# Sheet1.net
KiCad netlist of a schematic drawn in Altium Designer
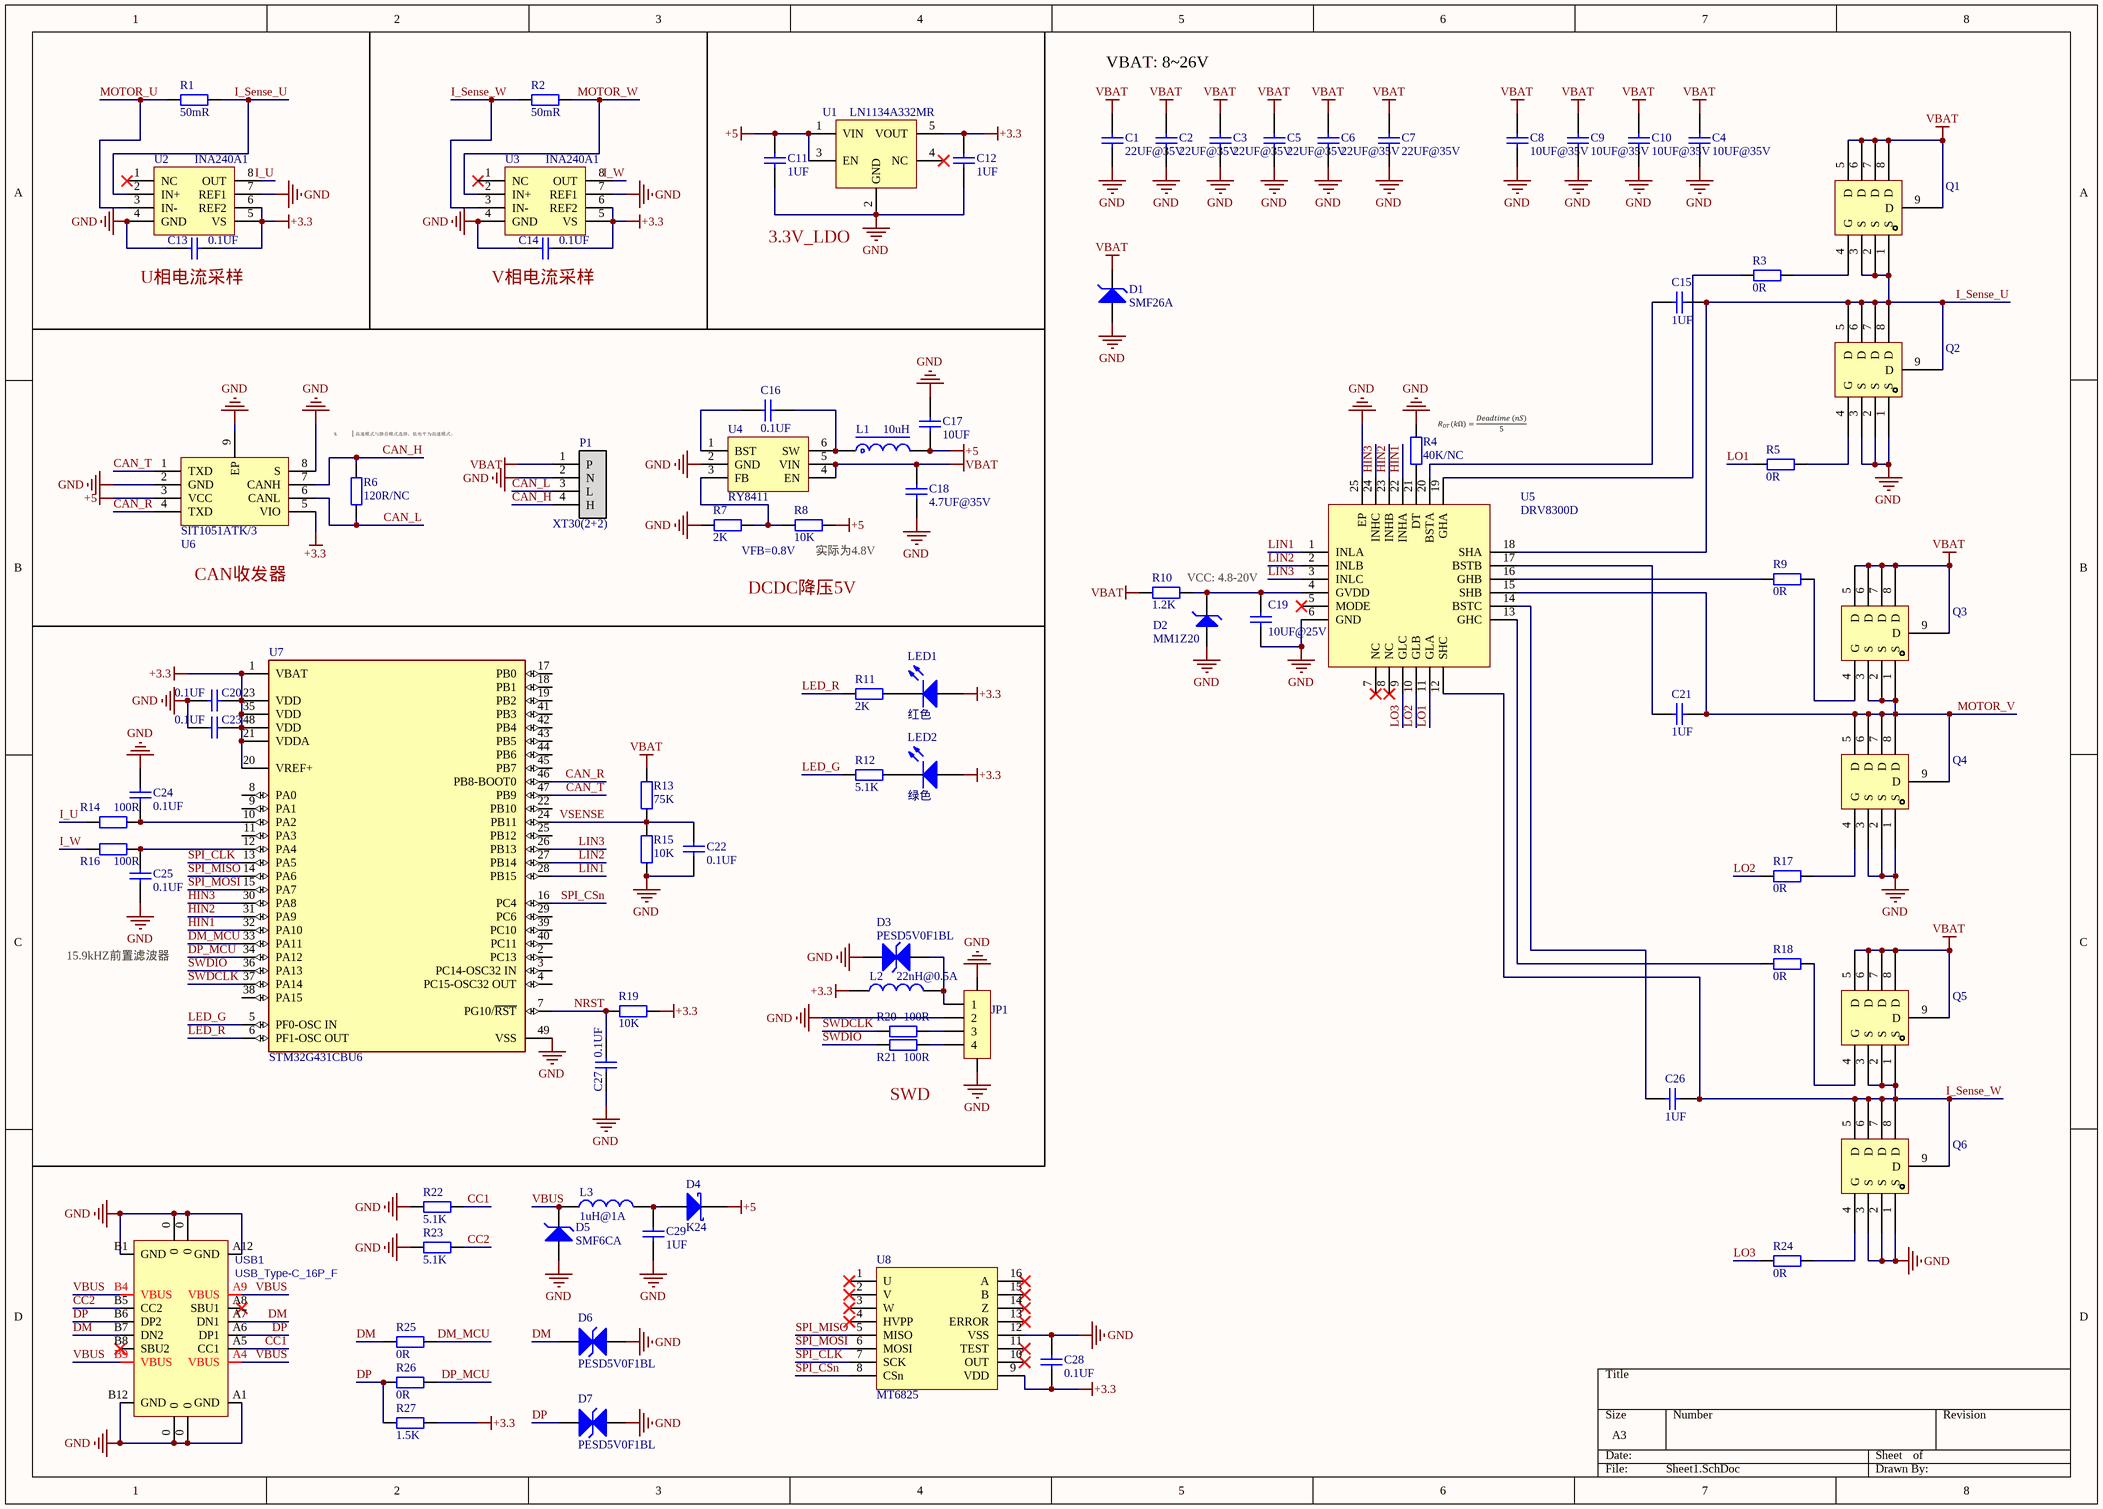
[diagram p0: Sheet1.SchDoc]

(export (version "E")
  (design (tool "Eeschema 10.0.6"))
  (components
    (comp (ref "C1")
      (value "22UF@35V")
      (footprint "C1206_NS")
      (description "贴片电容/MLCC电容")
      (libsource (lib "阻容") (part "C"))
    )
    (comp (ref "C2")
      (value "22UF@35V")
      (footprint "C1206_NS")
      (description "贴片电容/MLCC电容")
      (libsource (lib "阻容") (part "C"))
    )
    (comp (ref "C3")
      (value "22UF@35V")
      (footprint "C1206_NS")
      (description "贴片电容/MLCC电容")
      (libsource (lib "阻容") (part "C"))
    )
    (comp (ref "C4")
      (value "10UF@35V")
      (footprint "C0805_NS")
      (description "贴片电容/MLCC电容")
      (libsource (lib "阻容") (part "C"))
    )
    (comp (ref "C5")
      (value "22UF@35V")
      (footprint "C1206_NS")
      (description "贴片电容/MLCC电容")
      (libsource (lib "阻容") (part "C"))
    )
    (comp (ref "C6")
      (value "22UF@35V")
      (footprint "C1206_NS")
      (description "贴片电容/MLCC电容")
      (libsource (lib "阻容") (part "C"))
    )
    (comp (ref "C7")
      (value "22UF@35V")
      (footprint "C1206_NS")
      (description "贴片电容/MLCC电容")
      (libsource (lib "阻容") (part "C"))
    )
    (comp (ref "C8")
      (value "10UF@35V")
      (footprint "C0805_NS")
      (description "贴片电容/MLCC电容")
      (libsource (lib "阻容") (part "C"))
    )
    (comp (ref "C9")
      (value "10UF@35V")
      (footprint "C0805_NS")
      (description "贴片电容/MLCC电容")
      (libsource (lib "阻容") (part "C"))
    )
    (comp (ref "C10")
      (value "10UF@35V")
      (footprint "C0805_NS")
      (description "贴片电容/MLCC电容")
      (libsource (lib "阻容") (part "C"))
    )
    (comp (ref "C11")
      (value "1UF")
      (footprint "C0402_NS")
      (description "贴片电容/MLCC电容")
      (libsource (lib "阻容") (part "C"))
    )
    (comp (ref "C12")
      (value "1UF")
      (footprint "C0402_NS")
      (description "贴片电容/MLCC电容")
      (libsource (lib "阻容") (part "C"))
    )
    (comp (ref "C13")
      (value "0.1UF")
      (footprint "C0402_NS")
      (description "贴片电容/MLCC电容")
      (libsource (lib "阻容") (part "C"))
    )
    (comp (ref "C14")
      (value "0.1UF")
      (footprint "C0402_NS")
      (description "贴片电容/MLCC电容")
      (libsource (lib "阻容") (part "C"))
    )
    (comp (ref "C15")
      (value "1UF")
      (footprint "C0603_NS")
      (description "贴片电容/MLCC电容")
      (libsource (lib "阻容") (part "C"))
    )
    (comp (ref "C16")
      (value "0.1UF")
      (footprint "C0402_NS")
      (description "贴片电容/MLCC电容")
      (libsource (lib "阻容") (part "C"))
    )
    (comp (ref "C17")
      (value "10UF")
      (footprint "C0805_NS")
      (description "贴片电容/MLCC电容")
      (libsource (lib "阻容") (part "C"))
    )
    (comp (ref "C18")
      (value "4.7UF@35V")
      (footprint "C0805_NS")
      (description "贴片电容/MLCC电容")
      (libsource (lib "阻容") (part "C"))
    )
    (comp (ref "C19")
      (value "10UF@25V")
      (footprint "C0603_NS")
      (description "贴片电容/MLCC电容")
      (libsource (lib "阻容") (part "C"))
    )
    (comp (ref "C20")
      (value "0.1UF")
      (footprint "C0402_NS")
      (description "贴片电容/MLCC电容")
      (libsource (lib "阻容") (part "C"))
    )
    (comp (ref "C21")
      (value "1UF")
      (footprint "C0603_NS")
      (description "贴片电容/MLCC电容")
      (libsource (lib "阻容") (part "C"))
    )
    (comp (ref "C22")
      (value "0.1UF")
      (footprint "C0402_NS")
      (description "贴片电容/MLCC电容")
      (libsource (lib "阻容") (part "C"))
    )
    (comp (ref "C23")
      (value "0.1UF")
      (footprint "C0402_NS")
      (description "贴片电容/MLCC电容")
      (libsource (lib "阻容") (part "C"))
    )
    (comp (ref "C24")
      (value "0.1UF")
      (footprint "C0402_NS")
      (description "贴片电容/MLCC电容")
      (libsource (lib "阻容") (part "C"))
    )
    (comp (ref "C25")
      (value "0.1UF")
      (footprint "C0402_NS")
      (description "贴片电容/MLCC电容")
      (libsource (lib "阻容") (part "C"))
    )
    (comp (ref "C26")
      (value "1UF")
      (footprint "C0603_NS")
      (description "贴片电容/MLCC电容")
      (libsource (lib "阻容") (part "C"))
    )
    (comp (ref "C27")
      (value "0.1UF")
      (footprint "C0402_NS")
      (description "贴片电容/MLCC电容")
      (libsource (lib "阻容") (part "C"))
    )
    (comp (ref "C28")
      (value "0.1UF")
      (footprint "C0402_NS")
      (description "贴片电容/MLCC电容")
      (libsource (lib "阻容") (part "C"))
    )
    (comp (ref "C29")
      (value "1UF")
      (footprint "C0603_NS")
      (description "贴片电容/MLCC电容")
      (libsource (lib "阻容") (part "C"))
    )
    (comp (ref "D1")
      (value "SMF26A")
      (footprint "SOD-123")
      (description "TVS通用")
      (libsource (lib "二极管(含LED)") (part "TVS"))
    )
    (comp (ref "D2")
      (value "MM1Z20")
      (footprint "SOD-123")
      (description "稳压二极管")
      (fields (field (name "VOLTAGE") "5.1V"))
      (libsource (lib "二极管(含LED)") (part "MM1ZXX"))
    )
    (comp (ref "D3")
      (value "PESD5V0F1BL")
      (footprint "DFN1002-2L_L1.0_W0.6_P0.7")
      (description "双向静电和浪涌保护(TVS/ESD)")
      (libsource (lib "二极管(含LED)") (part "PESD5V0F1BL"))
    )
    (comp (ref "D4")
      (value "K24")
      (footprint "SOD-123")
      (description "肖特基二极管")
      (libsource (lib "二极管(含LED)") (part "SSXX"))
    )
    (comp (ref "D5")
      (value "SMF6CA")
      (footprint "SOD-123")
      (description "TVS通用")
      (libsource (lib "二极管(含LED)") (part "TVS"))
    )
    (comp (ref "D6")
      (value "PESD5V0F1BL")
      (footprint "DFN1002-2L_L1.0_W0.6_P0.7")
      (description "双向静电和浪涌保护(TVS/ESD)")
      (libsource (lib "二极管(含LED)") (part "PESD5V0F1BL"))
    )
    (comp (ref "D7")
      (value "PESD5V0F1BL")
      (footprint "DFN1002-2L_L1.0_W0.6_P0.7")
      (description "双向静电和浪涌保护(TVS/ESD)")
      (libsource (lib "二极管(含LED)") (part "PESD5V0F1BL"))
    )
    (comp (ref "JP1")
      (value "CON-4P")
      (footprint "HC0.8-WT-4P")
      (description "4P连接器")
      (libsource (lib "0.80mm连接器") (part "Header 4"))
    )
    (comp (ref "L1")
      (value "10uH")
      (footprint "NR3015")
      (description "太诱-NR磁胶电感")
      (libsource (lib "电感") (part "L-NR"))
    )
    (comp (ref "L2")
      (value "22nH@0.5A")
      (footprint "L0402_NS")
      (description "小功率贴片电感")
      (libsource (lib "电感") (part "L"))
    )
    (comp (ref "L3")
      (value "1uH@1A")
      (footprint "L1206_NS")
      (description "小功率贴片电感")
      (libsource (lib "电感") (part "L"))
    )
    (comp (ref "LED1")
      (value "红色")
      (footprint "LED0402_NS")
      (description "贴片LED")
      (libsource (lib "二极管(含LED)") (part "LED"))
    )
    (comp (ref "LED2")
      (value "绿色")
      (footprint "LED0402_NS")
      (description "贴片LED")
      (libsource (lib "二极管(含LED)") (part "LED"))
    )
    (comp (ref "P1")
      (value "XT30(2+2)")
      (footprint "XT30(2+2)PW-M")
      (description "XT30(2+2)连接器")
      (libsource (lib "接口") (part "XT30(2+2)"))
    )
    (comp (ref "Q1")
      (value "WSD3066DN33")
      (footprint "DFN8_L3.3_W3.3_P0.65")
      (libsource (lib "三极管-MOS管") (part "WSD3066DN33"))
    )
    (comp (ref "Q2")
      (value "WSD3066DN33")
      (footprint "DFN8_L3.3_W3.3_P0.65")
      (libsource (lib "三极管-MOS管") (part "WSD3066DN33"))
    )
    (comp (ref "Q3")
      (value "WSD3066DN33")
      (footprint "DFN8_L3.3_W3.3_P0.65")
      (libsource (lib "三极管-MOS管") (part "WSD3066DN33"))
    )
    (comp (ref "Q4")
      (value "WSD3066DN33")
      (footprint "DFN8_L3.3_W3.3_P0.65")
      (libsource (lib "三极管-MOS管") (part "WSD3066DN33"))
    )
    (comp (ref "Q5")
      (value "WSD3066DN33")
      (footprint "DFN8_L3.3_W3.3_P0.65")
      (libsource (lib "三极管-MOS管") (part "WSD3066DN33"))
    )
    (comp (ref "Q6")
      (value "WSD3066DN33")
      (footprint "DFN8_L3.3_W3.3_P0.65")
      (libsource (lib "三极管-MOS管") (part "WSD3066DN33"))
    )
    (comp (ref "R1")
      (value "50mR")
      (footprint "R1206_NS")
      (description "贴片电阻")
      (libsource (lib "阻容") (part "R"))
    )
    (comp (ref "R2")
      (value "50mR")
      (footprint "R1206_NS")
      (description "贴片电阻")
      (libsource (lib "阻容") (part "R"))
    )
    (comp (ref "R3")
      (value "0R")
      (footprint "R0402_NS")
      (description "贴片电阻")
      (libsource (lib "阻容") (part "R"))
    )
    (comp (ref "R4")
      (value "40K/NC")
      (footprint "R0402_NS")
      (description "贴片电阻")
      (libsource (lib "阻容") (part "R"))
    )
    (comp (ref "R5")
      (value "0R")
      (footprint "R0402_NS")
      (description "贴片电阻")
      (libsource (lib "阻容") (part "R"))
    )
    (comp (ref "R6")
      (value "120R/NC")
      (footprint "R0603_NS")
      (description "贴片电阻")
      (libsource (lib "阻容") (part "R"))
    )
    (comp (ref "R7")
      (value "2K")
      (footprint "R0402_NS")
      (description "贴片电阻")
      (libsource (lib "阻容") (part "R"))
    )
    (comp (ref "R8")
      (value "10K")
      (footprint "R0402_NS")
      (description "贴片电阻")
      (libsource (lib "阻容") (part "R"))
    )
    (comp (ref "R9")
      (value "0R")
      (footprint "R0402_NS")
      (description "贴片电阻")
      (libsource (lib "阻容") (part "R"))
    )
    (comp (ref "R10")
      (value "1.2K")
      (footprint "R0603_NS")
      (description "贴片电阻")
      (libsource (lib "阻容") (part "R"))
    )
    (comp (ref "R11")
      (value "2K")
      (footprint "R0402_NS")
      (description "贴片电阻")
      (libsource (lib "阻容") (part "R"))
    )
    (comp (ref "R12")
      (value "5.1K")
      (footprint "R0402_NS")
      (description "贴片电阻")
      (libsource (lib "阻容") (part "R"))
    )
    (comp (ref "R13")
      (value "75K")
      (footprint "R0402_NS")
      (description "贴片电阻")
      (libsource (lib "阻容") (part "R"))
    )
    (comp (ref "R14")
      (value "100R")
      (footprint "R0402_NS")
      (description "贴片电阻")
      (libsource (lib "阻容") (part "R"))
    )
    (comp (ref "R15")
      (value "10K")
      (footprint "R0402_NS")
      (description "贴片电阻")
      (libsource (lib "阻容") (part "R"))
    )
    (comp (ref "R16")
      (value "100R")
      (footprint "R0402_NS")
      (description "贴片电阻")
      (libsource (lib "阻容") (part "R"))
    )
    (comp (ref "R17")
      (value "0R")
      (footprint "R0402_NS")
      (description "贴片电阻")
      (libsource (lib "阻容") (part "R"))
    )
    (comp (ref "R18")
      (value "0R")
      (footprint "R0402_NS")
      (description "贴片电阻")
      (libsource (lib "阻容") (part "R"))
    )
    (comp (ref "R19")
      (value "10K")
      (footprint "R0402_NS")
      (description "贴片电阻")
      (libsource (lib "阻容") (part "R"))
    )
    (comp (ref "R20")
      (value "100R")
      (footprint "R0402_NS")
      (description "贴片电阻")
      (libsource (lib "阻容") (part "R"))
    )
    (comp (ref "R21")
      (value "100R")
      (footprint "R0402_NS")
      (description "贴片电阻")
      (libsource (lib "阻容") (part "R"))
    )
    (comp (ref "R22")
      (value "5.1K")
      (footprint "R0402_NS")
      (description "贴片电阻")
      (libsource (lib "阻容") (part "R"))
    )
    (comp (ref "R23")
      (value "5.1K")
      (footprint "R0402_NS")
      (description "贴片电阻")
      (libsource (lib "阻容") (part "R"))
    )
    (comp (ref "R24")
      (value "0R")
      (footprint "R0402_NS")
      (description "贴片电阻")
      (libsource (lib "阻容") (part "R"))
    )
    (comp (ref "R25")
      (value "0R")
      (footprint "R0402_NS")
      (description "贴片电阻")
      (libsource (lib "阻容") (part "R"))
    )
    (comp (ref "R26")
      (value "0R")
      (footprint "R0402_NS")
      (description "贴片电阻")
      (libsource (lib "阻容") (part "R"))
    )
    (comp (ref "R27")
      (value "1.5K")
      (footprint "R0402_NS")
      (description "贴片电阻")
      (libsource (lib "阻容") (part "R"))
    )
    (comp (ref "U1")
      (value "LN1134A332MR")
      (footprint "SOT23-5_L3.0_W1.7_P0.95")
      (libsource (lib "LDO") (part "RT9013-33GB"))
    )
    (comp (ref "U2")
      (value "INA240A1")
      (footprint "TSSOP8_L4.4_W3.0_P0.65")
      (description "具有增强的 PWM 抑制能力的 -4V 至 80V、双向、超精密电流感应放大器")
      (libsource (lib "运放") (part "INA240"))
    )
    (comp (ref "U3")
      (value "INA240A1")
      (footprint "TSSOP8_L4.4_W3.0_P0.65")
      (description "具有增强的 PWM 抑制能力的 -4V 至 80V、双向、超精密电流感应放大器")
      (libsource (lib "运放") (part "INA240"))
    )
    (comp (ref "U4")
      (value "RY8411")
      (footprint "SOT23-6_L3.0_W1.7_P0.95")
      (description "40V/1A/1.1MHz同步降压转换器")
      (libsource (lib "电源IC") (part "JW5026"))
    )
    (comp (ref "U5")
      (value "DRV8300D")
      (footprint "QFN24_L4.0_W4.0_P0.5")
      (description "具有自举二极管的最大 100V 简单三相栅极驱动器")
      (libsource (lib "电机驱动IC") (part "DRV8300D"))
    )
    (comp (ref "U6")
      (value "SIT1051ATK/3")
      (footprint "DFN8_L3.0_W3.0_P0.65")
      (description "5V 供电， IO 口兼容 3.3V，± 70V 总线耐压， CAN FD 静音模式总线收发器")
      (libsource (lib "协议芯片") (part "SIT1051ATK/3"))
    )
    (comp (ref "U7")
      (value "STM32G431CBU6")
      (footprint "QFN48_L7.0_W7.0_P0.5")
      (description "Microcontroller 32-Bit ARM Cortex-M4 RISC 128KB Flash 1.71V to 3.6V QFN48")
      (fields
        (field (name "MANUFACTURER") "STMicroelectronics")
        (field (name "OCTOPART") "https://octopart.com/stm32g431cbt6-stmicroelectronics-98835224")
      )
      (libsource (lib "2.1 - STM32 G0及G4系列单片机") (part "STM32G431CBU6"))
    )
    (comp (ref "U8")
      (value "MT6825")
      (footprint "TSSOP16_L5.0_W4.4_P0.65")
      (description "18位高分辨率、高速磁性角度编码器IC")
      (libsource (lib "其他") (part "MT6825"))
    )
    (comp (ref "USB1")
      (value "USB_Type-C_16P_F")
      (footprint "USB_Type-C_SMD_16P_F")
      (description "USB_Type-C母座")
      (libsource (lib "接口") (part "USB_Type-C_16P_F"))
    )
  )
  (nets
    (net (code "1") (name "+3.3") (class "Default")
      (node (ref "C12") (pin "2") (pinfunction "2_2") (pintype "passive"))
      (node (ref "C13") (pin "2") (pinfunction "2_2") (pintype "passive"))
      (node (ref "C14") (pin "2") (pinfunction "2_2") (pintype "passive"))
      (node (ref "C20") (pin "1") (pinfunction "1_1") (pintype "passive"))
      (node (ref "C23") (pin "1") (pinfunction "1_1") (pintype "passive"))
      (node (ref "C28") (pin "2") (pinfunction "2_2") (pintype "passive"))
      (node (ref "L2") (pin "1") (pinfunction "1_1") (pintype "passive"))
      (node (ref "LED1") (pin "1") (pinfunction "A_1") (pintype "passive"))
      (node (ref "LED2") (pin "1") (pinfunction "A_1") (pintype "passive"))
      (node (ref "R19") (pin "2") (pinfunction "2_2") (pintype "passive"))
      (node (ref "R27") (pin "2") (pinfunction "2_2") (pintype "passive"))
      (node (ref "U1") (pin "5") (pinfunction "VOUT_5") (pintype "passive"))
      (node (ref "U2") (pin "5") (pinfunction "VS_5") (pintype "passive"))
      (node (ref "U2") (pin "6") (pinfunction "REF2_6") (pintype "passive"))
      (node (ref "U3") (pin "5") (pinfunction "VS_5") (pintype "passive"))
      (node (ref "U3") (pin "6") (pinfunction "REF2_6") (pintype "passive"))
      (node (ref "U6") (pin "5") (pinfunction "VIO_5") (pintype "passive"))
      (node (ref "U7") (pin "1") (pinfunction "VBAT_1") (pintype "power_in"))
      (node (ref "U7") (pin "20") (pinfunction "VREF+_20") (pintype "power_in"))
      (node (ref "U7") (pin "21") (pinfunction "VDDA_21") (pintype "power_in"))
      (node (ref "U7") (pin "23") (pinfunction "VDD_23") (pintype "power_in"))
      (node (ref "U7") (pin "35") (pinfunction "VDD_35") (pintype "power_in"))
      (node (ref "U7") (pin "48") (pinfunction "VDD_48") (pintype "power_in"))
      (node (ref "U8") (pin "9") (pinfunction "VDD_9") (pintype "passive"))
    )
    (net (code "2") (name "+5") (class "Default")
      (node (ref "C11") (pin "2") (pinfunction "2_2") (pintype "passive"))
      (node (ref "C17") (pin "2") (pinfunction "2_2") (pintype "passive"))
      (node (ref "D4") (pin "2") (pinfunction "K_2") (pintype "passive"))
      (node (ref "L1") (pin "2") (pinfunction "2_2") (pintype "passive"))
      (node (ref "R8") (pin "1") (pinfunction "1_1") (pintype "passive"))
      (node (ref "U1") (pin "1") (pinfunction "VIN_1") (pintype "passive"))
      (node (ref "U1") (pin "3") (pinfunction "EN_3") (pintype "passive"))
      (node (ref "U6") (pin "3") (pinfunction "VCC_3") (pintype "passive"))
    )
    (net (code "3") (name "/CAN_H") (class "Default")
      (node (ref "P1") (pin "4") (pinfunction "H_4") (pintype "passive"))
      (node (ref "R6") (pin "2") (pinfunction "2_2") (pintype "passive"))
      (node (ref "U6") (pin "7") (pinfunction "CANH_7") (pintype "passive"))
    )
    (net (code "4") (name "/CAN_L") (class "Default")
      (node (ref "P1") (pin "3") (pinfunction "L_3") (pintype "passive"))
      (node (ref "R6") (pin "1") (pinfunction "1_1") (pintype "passive"))
      (node (ref "U6") (pin "6") (pinfunction "CANL_6") (pintype "passive"))
    )
    (net (code "5") (name "/CAN_R") (class "Default")
      (node (ref "U6") (pin "4") (pinfunction "TXD_4") (pintype "passive"))
      (node (ref "U7") (pin "46") (pinfunction "PB8-BOOT0_46") (pintype "bidirectional"))
    )
    (net (code "6") (name "/CAN_T") (class "Default")
      (node (ref "U6") (pin "1") (pinfunction "TXD_1") (pintype "passive"))
      (node (ref "U7") (pin "47") (pinfunction "PB9_47") (pintype "bidirectional"))
    )
    (net (code "7") (name "/CC1") (class "Default")
      (node (ref "R22") (pin "2") (pinfunction "2_2") (pintype "passive"))
      (node (ref "USB1") (pin "A5") (pinfunction "CC1_A5") (pintype "passive"))
    )
    (net (code "8") (name "/CC2") (class "Default")
      (node (ref "R23") (pin "2") (pinfunction "2_2") (pintype "passive"))
      (node (ref "USB1") (pin "B5") (pinfunction "CC2_B5") (pintype "passive"))
    )
    (net (code "9") (name "/DM") (class "Default")
      (node (ref "D6") (pin "1") (pinfunction "A_1") (pintype "passive"))
      (node (ref "R25") (pin "1") (pinfunction "1_1") (pintype "passive"))
      (node (ref "USB1") (pin "A7") (pinfunction "DN1_A7") (pintype "passive"))
      (node (ref "USB1") (pin "B7") (pinfunction "DN2_B7") (pintype "passive"))
    )
    (net (code "10") (name "/DM_MCU") (class "Default")
      (node (ref "R25") (pin "2") (pinfunction "2_2") (pintype "passive"))
      (node (ref "U7") (pin "33") (pinfunction "PA11_33") (pintype "bidirectional"))
    )
    (net (code "11") (name "/DP") (class "Default")
      (node (ref "D7") (pin "1") (pinfunction "A_1") (pintype "passive"))
      (node (ref "R26") (pin "1") (pinfunction "1_1") (pintype "passive"))
      (node (ref "R27") (pin "1") (pinfunction "1_1") (pintype "passive"))
      (node (ref "USB1") (pin "A6") (pinfunction "DP1_A6") (pintype "passive"))
      (node (ref "USB1") (pin "B6") (pinfunction "DP2_B6") (pintype "passive"))
    )
    (net (code "12") (name "/DP_MCU") (class "Default")
      (node (ref "R26") (pin "2") (pinfunction "2_2") (pintype "passive"))
      (node (ref "U7") (pin "34") (pinfunction "PA12_34") (pintype "bidirectional"))
    )
    (net (code "13") (name "/HIN1") (class "Default")
      (node (ref "U5") (pin "22") (pinfunction "INHA_22") (pintype "passive"))
      (node (ref "U7") (pin "32") (pinfunction "PA10_32") (pintype "bidirectional"))
    )
    (net (code "14") (name "/HIN2") (class "Default")
      (node (ref "U5") (pin "23") (pinfunction "INHB_23") (pintype "passive"))
      (node (ref "U7") (pin "31") (pinfunction "PA9_31") (pintype "bidirectional"))
    )
    (net (code "15") (name "/HIN3") (class "Default")
      (node (ref "U5") (pin "24") (pinfunction "INHC_24") (pintype "passive"))
      (node (ref "U7") (pin "30") (pinfunction "PA8_30") (pintype "bidirectional"))
    )
    (net (code "16") (name "/I_Sense_U") (class "Default")
      (node (ref "C15") (pin "1") (pinfunction "1_1") (pintype "passive"))
      (node (ref "Q1") (pin "1") (pinfunction "S_1") (pintype "passive"))
      (node (ref "Q1") (pin "2") (pinfunction "S_2") (pintype "passive"))
      (node (ref "Q1") (pin "3") (pinfunction "S_3") (pintype "passive"))
      (node (ref "Q2") (pin "5") (pinfunction "D_5") (pintype "passive"))
      (node (ref "Q2") (pin "6") (pinfunction "D_6") (pintype "passive"))
      (node (ref "Q2") (pin "7") (pinfunction "D_7") (pintype "passive"))
      (node (ref "Q2") (pin "8") (pinfunction "D_8") (pintype "passive"))
      (node (ref "Q2") (pin "9") (pinfunction "D_9") (pintype "passive"))
      (node (ref "R1") (pin "1") (pinfunction "1_1") (pintype "passive"))
      (node (ref "U2") (pin "2") (pinfunction "IN+_2") (pintype "passive"))
      (node (ref "U5") (pin "18") (pinfunction "SHA_18") (pintype "passive"))
    )
    (net (code "17") (name "/I_Sense_W") (class "Default")
      (node (ref "C26") (pin "1") (pinfunction "1_1") (pintype "passive"))
      (node (ref "Q5") (pin "1") (pinfunction "S_1") (pintype "passive"))
      (node (ref "Q5") (pin "2") (pinfunction "S_2") (pintype "passive"))
      (node (ref "Q5") (pin "3") (pinfunction "S_3") (pintype "passive"))
      (node (ref "Q6") (pin "5") (pinfunction "D_5") (pintype "passive"))
      (node (ref "Q6") (pin "6") (pinfunction "D_6") (pintype "passive"))
      (node (ref "Q6") (pin "7") (pinfunction "D_7") (pintype "passive"))
      (node (ref "Q6") (pin "8") (pinfunction "D_8") (pintype "passive"))
      (node (ref "Q6") (pin "9") (pinfunction "D_9") (pintype "passive"))
      (node (ref "R2") (pin "2") (pinfunction "2_2") (pintype "passive"))
      (node (ref "U3") (pin "3") (pinfunction "IN-_3") (pintype "passive"))
      (node (ref "U5") (pin "12") (pinfunction "SHC_12") (pintype "passive"))
    )
    (net (code "18") (name "/I_U") (class "Default")
      (node (ref "R14") (pin "2") (pinfunction "2_2") (pintype "passive"))
      (node (ref "U2") (pin "8") (pinfunction "OUT_8") (pintype "passive"))
    )
    (net (code "19") (name "/I_W") (class "Default")
      (node (ref "R16") (pin "2") (pinfunction "2_2") (pintype "passive"))
      (node (ref "U3") (pin "8") (pinfunction "OUT_8") (pintype "passive"))
    )
    (net (code "20") (name "/LED_G") (class "Default")
      (node (ref "R12") (pin "1") (pinfunction "1_1") (pintype "passive"))
      (node (ref "U7") (pin "5") (pinfunction "PF0-OSC_IN_5") (pintype "bidirectional"))
    )
    (net (code "21") (name "/LED_R") (class "Default")
      (node (ref "R11") (pin "1") (pinfunction "1_1") (pintype "passive"))
      (node (ref "U7") (pin "6") (pinfunction "PF1-OSC_OUT_6") (pintype "bidirectional"))
    )
    (net (code "22") (name "/LIN1") (class "Default")
      (node (ref "U5") (pin "1") (pinfunction "INLA_1") (pintype "passive"))
      (node (ref "U7") (pin "28") (pinfunction "PB15_28") (pintype "bidirectional"))
    )
    (net (code "23") (name "/LIN2") (class "Default")
      (node (ref "U5") (pin "2") (pinfunction "INLB_2") (pintype "passive"))
      (node (ref "U7") (pin "27") (pinfunction "PB14_27") (pintype "bidirectional"))
    )
    (net (code "24") (name "/LIN3") (class "Default")
      (node (ref "U5") (pin "3") (pinfunction "INLC_3") (pintype "passive"))
      (node (ref "U7") (pin "26") (pinfunction "PB13_26") (pintype "bidirectional"))
    )
    (net (code "25") (name "/LO1") (class "Default")
      (node (ref "R5") (pin "1") (pinfunction "1_1") (pintype "passive"))
      (node (ref "U5") (pin "11") (pinfunction "GLA_11") (pintype "passive"))
    )
    (net (code "26") (name "/LO2") (class "Default")
      (node (ref "R17") (pin "1") (pinfunction "1_1") (pintype "passive"))
      (node (ref "U5") (pin "10") (pinfunction "GLB_10") (pintype "passive"))
    )
    (net (code "27") (name "/LO3") (class "Default")
      (node (ref "R24") (pin "1") (pinfunction "1_1") (pintype "passive"))
      (node (ref "U5") (pin "9") (pinfunction "GLC_9") (pintype "passive"))
    )
    (net (code "28") (name "/MOTOR_U") (class "Default")
      (node (ref "R1") (pin "2") (pinfunction "2_2") (pintype "passive"))
      (node (ref "U2") (pin "3") (pinfunction "IN-_3") (pintype "passive"))
    )
    (net (code "29") (name "/MOTOR_V") (class "Default")
      (node (ref "C21") (pin "1") (pinfunction "1_1") (pintype "passive"))
      (node (ref "Q3") (pin "1") (pinfunction "S_1") (pintype "passive"))
      (node (ref "Q3") (pin "2") (pinfunction "S_2") (pintype "passive"))
      (node (ref "Q3") (pin "3") (pinfunction "S_3") (pintype "passive"))
      (node (ref "Q4") (pin "5") (pinfunction "D_5") (pintype "passive"))
      (node (ref "Q4") (pin "6") (pinfunction "D_6") (pintype "passive"))
      (node (ref "Q4") (pin "7") (pinfunction "D_7") (pintype "passive"))
      (node (ref "Q4") (pin "8") (pinfunction "D_8") (pintype "passive"))
      (node (ref "Q4") (pin "9") (pinfunction "D_9") (pintype "passive"))
      (node (ref "U5") (pin "15") (pinfunction "SHB_15") (pintype "passive"))
    )
    (net (code "30") (name "/MOTOR_W") (class "Default")
      (node (ref "R2") (pin "1") (pinfunction "1_1") (pintype "passive"))
      (node (ref "U3") (pin "2") (pinfunction "IN+_2") (pintype "passive"))
    )
    (net (code "31") (name "/NRST") (class "Default")
      (node (ref "C27") (pin "2") (pinfunction "2_2") (pintype "passive"))
      (node (ref "R19") (pin "1") (pinfunction "1_1") (pintype "passive"))
      (node (ref "U7") (pin "7") (pinfunction "PG10/~{RST}_7") (pintype "bidirectional"))
    )
    (net (code "32") (name "/SPI_CLK") (class "Default")
      (node (ref "U7") (pin "13") (pinfunction "PA5_13") (pintype "bidirectional"))
      (node (ref "U8") (pin "7") (pinfunction "SCK_7") (pintype "passive"))
    )
    (net (code "33") (name "/SPI_CSn") (class "Default")
      (node (ref "U7") (pin "16") (pinfunction "PC4_16") (pintype "bidirectional"))
      (node (ref "U8") (pin "8") (pinfunction "CSn_8") (pintype "passive"))
    )
    (net (code "34") (name "/SPI_MISO") (class "Default")
      (node (ref "U7") (pin "14") (pinfunction "PA6_14") (pintype "bidirectional"))
      (node (ref "U8") (pin "5") (pinfunction "MISO_5") (pintype "passive"))
    )
    (net (code "35") (name "/SPI_MOSI") (class "Default")
      (node (ref "U7") (pin "15") (pinfunction "PA7_15") (pintype "bidirectional"))
      (node (ref "U8") (pin "6") (pinfunction "MOSI_6") (pintype "passive"))
    )
    (net (code "36") (name "/SWDCLK") (class "Default")
      (node (ref "R20") (pin "1") (pinfunction "1_1") (pintype "passive"))
      (node (ref "U7") (pin "37") (pinfunction "PA14_37") (pintype "bidirectional"))
    )
    (net (code "37") (name "/SWDIO") (class "Default")
      (node (ref "R21") (pin "1") (pinfunction "1_1") (pintype "passive"))
      (node (ref "U7") (pin "36") (pinfunction "PA13_36") (pintype "bidirectional"))
    )
    (net (code "38") (name "/VBUS") (class "Default")
      (node (ref "D5") (pin "2") (pinfunction "K_2") (pintype "passive"))
      (node (ref "L3") (pin "1") (pinfunction "1_1") (pintype "passive"))
      (node (ref "USB1") (pin "A4") (pinfunction "VBUS_A4") (pintype "passive"))
      (node (ref "USB1") (pin "A9") (pinfunction "VBUS_A9") (pintype "passive"))
      (node (ref "USB1") (pin "B4") (pinfunction "VBUS_B4") (pintype "passive"))
      (node (ref "USB1") (pin "B9") (pinfunction "VBUS_B9") (pintype "passive"))
    )
    (net (code "39") (name "/VSENSE") (class "Default")
      (node (ref "C22") (pin "1") (pinfunction "1_1") (pintype "passive"))
      (node (ref "R13") (pin "1") (pinfunction "1_1") (pintype "passive"))
      (node (ref "R15") (pin "2") (pinfunction "2_2") (pintype "passive"))
      (node (ref "U7") (pin "24") (pinfunction "PB11_24") (pintype "bidirectional"))
    )
    (net (code "40") (name "GND") (class "Default")
      (node (ref "C1") (pin "2") (pinfunction "2_2") (pintype "passive"))
      (node (ref "C10") (pin "2") (pinfunction "2_2") (pintype "passive"))
      (node (ref "C11") (pin "1") (pinfunction "1_1") (pintype "passive"))
      (node (ref "C12") (pin "1") (pinfunction "1_1") (pintype "passive"))
      (node (ref "C13") (pin "1") (pinfunction "1_1") (pintype "passive"))
      (node (ref "C14") (pin "1") (pinfunction "1_1") (pintype "passive"))
      (node (ref "C17") (pin "1") (pinfunction "1_1") (pintype "passive"))
      (node (ref "C18") (pin "1") (pinfunction "1_1") (pintype "passive"))
      (node (ref "C19") (pin "1") (pinfunction "1_1") (pintype "passive"))
      (node (ref "C2") (pin "2") (pinfunction "2_2") (pintype "passive"))
      (node (ref "C20") (pin "2") (pinfunction "2_2") (pintype "passive"))
      (node (ref "C22") (pin "2") (pinfunction "2_2") (pintype "passive"))
      (node (ref "C23") (pin "2") (pinfunction "2_2") (pintype "passive"))
      (node (ref "C24") (pin "1") (pinfunction "1_1") (pintype "passive"))
      (node (ref "C25") (pin "2") (pinfunction "2_2") (pintype "passive"))
      (node (ref "C27") (pin "1") (pinfunction "1_1") (pintype "passive"))
      (node (ref "C28") (pin "1") (pinfunction "1_1") (pintype "passive"))
      (node (ref "C29") (pin "1") (pinfunction "1_1") (pintype "passive"))
      (node (ref "C3") (pin "2") (pinfunction "2_2") (pintype "passive"))
      (node (ref "C4") (pin "2") (pinfunction "2_2") (pintype "passive"))
      (node (ref "C5") (pin "2") (pinfunction "2_2") (pintype "passive"))
      (node (ref "C6") (pin "2") (pinfunction "2_2") (pintype "passive"))
      (node (ref "C7") (pin "2") (pinfunction "2_2") (pintype "passive"))
      (node (ref "C8") (pin "2") (pinfunction "2_2") (pintype "passive"))
      (node (ref "C9") (pin "2") (pinfunction "2_2") (pintype "passive"))
      (node (ref "D1") (pin "1") (pinfunction "A_1") (pintype "passive"))
      (node (ref "D2") (pin "1") (pinfunction "A_1") (pintype "passive"))
      (node (ref "D3") (pin "2") (pinfunction "K_2") (pintype "passive"))
      (node (ref "D5") (pin "1") (pinfunction "A_1") (pintype "passive"))
      (node (ref "D6") (pin "2") (pinfunction "K_2") (pintype "passive"))
      (node (ref "D7") (pin "2") (pinfunction "K_2") (pintype "passive"))
      (node (ref "JP1") (pin "0") (pinfunction "0_0") (pintype "passive"))
      (node (ref "JP1") (pin "2") (pinfunction "2_2") (pintype "passive"))
      (node (ref "P1") (pin "2") (pinfunction "N_2") (pintype "passive"))
      (node (ref "Q2") (pin "1") (pinfunction "S_1") (pintype "passive"))
      (node (ref "Q2") (pin "2") (pinfunction "S_2") (pintype "passive"))
      (node (ref "Q2") (pin "3") (pinfunction "S_3") (pintype "passive"))
      (node (ref "Q4") (pin "1") (pinfunction "S_1") (pintype "passive"))
      (node (ref "Q4") (pin "2") (pinfunction "S_2") (pintype "passive"))
      (node (ref "Q4") (pin "3") (pinfunction "S_3") (pintype "passive"))
      (node (ref "Q6") (pin "1") (pinfunction "S_1") (pintype "passive"))
      (node (ref "Q6") (pin "2") (pinfunction "S_2") (pintype "passive"))
      (node (ref "Q6") (pin "3") (pinfunction "S_3") (pintype "passive"))
      (node (ref "R15") (pin "1") (pinfunction "1_1") (pintype "passive"))
      (node (ref "R22") (pin "1") (pinfunction "1_1") (pintype "passive"))
      (node (ref "R23") (pin "1") (pinfunction "1_1") (pintype "passive"))
      (node (ref "R4") (pin "2") (pinfunction "2_2") (pintype "passive"))
      (node (ref "R7") (pin "2") (pinfunction "2_2") (pintype "passive"))
      (node (ref "U1") (pin "2") (pinfunction "GND_2") (pintype "passive"))
      (node (ref "U2") (pin "4") (pinfunction "GND_4") (pintype "passive"))
      (node (ref "U2") (pin "7") (pinfunction "REF1_7") (pintype "passive"))
      (node (ref "U3") (pin "4") (pinfunction "GND_4") (pintype "passive"))
      (node (ref "U3") (pin "7") (pinfunction "REF1_7") (pintype "passive"))
      (node (ref "U4") (pin "2") (pinfunction "GND_2") (pintype "passive"))
      (node (ref "U5") (pin "25") (pinfunction "EP_25") (pintype "passive"))
      (node (ref "U5") (pin "6") (pinfunction "GND_6") (pintype "passive"))
      (node (ref "U6") (pin "2") (pinfunction "GND_2") (pintype "passive"))
      (node (ref "U6") (pin "8") (pinfunction "S_8") (pintype "passive"))
      (node (ref "U6") (pin "9") (pinfunction "EP_9") (pintype "passive"))
      (node (ref "U7") (pin "49") (pinfunction "VSS_49") (pintype "power_in"))
      (node (ref "U8") (pin "12") (pinfunction "VSS_12") (pintype "passive"))
      (node (ref "USB1") (pin "0") (pinfunction "0_0") (pintype "passive"))
      (node (ref "USB1") (pin "A1") (pinfunction "GND_A1") (pintype "passive"))
      (node (ref "USB1") (pin "A12") (pinfunction "GND_A12") (pintype "passive"))
      (node (ref "USB1") (pin "B1") (pinfunction "GND_B1") (pintype "passive"))
      (node (ref "USB1") (pin "B12") (pinfunction "GND_B12") (pintype "passive"))
    )
    (net (code "41") (name "Net-(D2-K)") (class "Default")
      (node (ref "C19") (pin "2") (pinfunction "2_2") (pintype "passive"))
      (node (ref "D2") (pin "2") (pinfunction "K_2") (pintype "passive"))
      (node (ref "R10") (pin "2") (pinfunction "2_2") (pintype "passive"))
      (node (ref "U5") (pin "4") (pinfunction "GVDD_4") (pintype "passive"))
    )
    (net (code "42") (name "Net-(D3-A)") (class "Default")
      (node (ref "D3") (pin "1") (pinfunction "A_1") (pintype "passive"))
      (node (ref "JP1") (pin "1") (pinfunction "1_1") (pintype "passive"))
      (node (ref "L2") (pin "2") (pinfunction "2_2") (pintype "passive"))
    )
    (net (code "43") (name "Net-(D4-A)") (class "Default")
      (node (ref "C29") (pin "2") (pinfunction "2_2") (pintype "passive"))
      (node (ref "D4") (pin "1") (pinfunction "A_1") (pintype "passive"))
      (node (ref "L3") (pin "2") (pinfunction "2_2") (pintype "passive"))
    )
    (net (code "44") (name "Net-(JP1-Pad3)") (class "Default")
      (node (ref "JP1") (pin "3") (pinfunction "3_3") (pintype "passive"))
      (node (ref "R20") (pin "2") (pinfunction "2_2") (pintype "passive"))
    )
    (net (code "45") (name "Net-(JP1-Pad4)") (class "Default")
      (node (ref "JP1") (pin "4") (pinfunction "4_4") (pintype "passive"))
      (node (ref "R21") (pin "2") (pinfunction "2_2") (pintype "passive"))
    )
    (net (code "46") (name "Net-(LED1-K)") (class "Default")
      (node (ref "LED1") (pin "2") (pinfunction "K_2") (pintype "passive"))
      (node (ref "R11") (pin "2") (pinfunction "2_2") (pintype "passive"))
    )
    (net (code "47") (name "Net-(LED2-K)") (class "Default")
      (node (ref "LED2") (pin "2") (pinfunction "K_2") (pintype "passive"))
      (node (ref "R12") (pin "2") (pinfunction "2_2") (pintype "passive"))
    )
    (net (code "48") (name "Net-(Q1-G)") (class "Default")
      (node (ref "Q1") (pin "4") (pinfunction "G_4") (pintype "passive"))
      (node (ref "R3") (pin "2") (pinfunction "2_2") (pintype "passive"))
    )
    (net (code "49") (name "Net-(Q2-G)") (class "Default")
      (node (ref "Q2") (pin "4") (pinfunction "G_4") (pintype "passive"))
      (node (ref "R5") (pin "2") (pinfunction "2_2") (pintype "passive"))
    )
    (net (code "50") (name "Net-(Q3-G)") (class "Default")
      (node (ref "Q3") (pin "4") (pinfunction "G_4") (pintype "passive"))
      (node (ref "R9") (pin "2") (pinfunction "2_2") (pintype "passive"))
    )
    (net (code "51") (name "Net-(Q4-G)") (class "Default")
      (node (ref "Q4") (pin "4") (pinfunction "G_4") (pintype "passive"))
      (node (ref "R17") (pin "2") (pinfunction "2_2") (pintype "passive"))
    )
    (net (code "52") (name "Net-(Q5-G)") (class "Default")
      (node (ref "Q5") (pin "4") (pinfunction "G_4") (pintype "passive"))
      (node (ref "R18") (pin "2") (pinfunction "2_2") (pintype "passive"))
    )
    (net (code "53") (name "Net-(Q6-G)") (class "Default")
      (node (ref "Q6") (pin "4") (pinfunction "G_4") (pintype "passive"))
      (node (ref "R24") (pin "2") (pinfunction "2_2") (pintype "passive"))
    )
    (net (code "54") (name "Net-(U4-BST)") (class "Default")
      (node (ref "C16") (pin "1") (pinfunction "1_1") (pintype "passive"))
      (node (ref "U4") (pin "1") (pinfunction "BST_1") (pintype "passive"))
    )
    (net (code "55") (name "Net-(U4-FB)") (class "Default")
      (node (ref "R7") (pin "1") (pinfunction "1_1") (pintype "passive"))
      (node (ref "R8") (pin "2") (pinfunction "2_2") (pintype "passive"))
      (node (ref "U4") (pin "3") (pinfunction "FB_3") (pintype "passive"))
    )
    (net (code "56") (name "Net-(U4-SW)") (class "Default")
      (node (ref "C16") (pin "2") (pinfunction "2_2") (pintype "passive"))
      (node (ref "L1") (pin "1") (pinfunction "1_1") (pintype "passive"))
      (node (ref "U4") (pin "6") (pinfunction "SW_6") (pintype "passive"))
    )
    (net (code "57") (name "Net-(U5-BSTA)") (class "Default")
      (node (ref "C15") (pin "2") (pinfunction "2_2") (pintype "passive"))
      (node (ref "U5") (pin "20") (pinfunction "BSTA_20") (pintype "passive"))
    )
    (net (code "58") (name "Net-(U5-BSTB)") (class "Default")
      (node (ref "C21") (pin "2") (pinfunction "2_2") (pintype "passive"))
      (node (ref "U5") (pin "17") (pinfunction "BSTB_17") (pintype "passive"))
    )
    (net (code "59") (name "Net-(U5-BSTC)") (class "Default")
      (node (ref "C26") (pin "2") (pinfunction "2_2") (pintype "passive"))
      (node (ref "U5") (pin "14") (pinfunction "BSTC_14") (pintype "passive"))
    )
    (net (code "60") (name "Net-(U5-DT)") (class "Default")
      (node (ref "R4") (pin "1") (pinfunction "1_1") (pintype "passive"))
      (node (ref "U5") (pin "21") (pinfunction "DT_21") (pintype "passive"))
    )
    (net (code "61") (name "Net-(U5-GHA)") (class "Default")
      (node (ref "R3") (pin "1") (pinfunction "1_1") (pintype "passive"))
      (node (ref "U5") (pin "19") (pinfunction "GHA_19") (pintype "passive"))
    )
    (net (code "62") (name "Net-(U5-GHB)") (class "Default")
      (node (ref "R9") (pin "1") (pinfunction "1_1") (pintype "passive"))
      (node (ref "U5") (pin "16") (pinfunction "GHB_16") (pintype "passive"))
    )
    (net (code "63") (name "Net-(U5-GHC)") (class "Default")
      (node (ref "R18") (pin "1") (pinfunction "1_1") (pintype "passive"))
      (node (ref "U5") (pin "13") (pinfunction "GHC_13") (pintype "passive"))
    )
    (net (code "64") (name "Net-(U7-PA2)") (class "Default")
      (node (ref "C24") (pin "2") (pinfunction "2_2") (pintype "passive"))
      (node (ref "R14") (pin "1") (pinfunction "1_1") (pintype "passive"))
      (node (ref "U7") (pin "10") (pinfunction "PA2_10") (pintype "bidirectional"))
    )
    (net (code "65") (name "Net-(U7-PA4)") (class "Default")
      (node (ref "C25") (pin "1") (pinfunction "1_1") (pintype "passive"))
      (node (ref "R16") (pin "1") (pinfunction "1_1") (pintype "passive"))
      (node (ref "U7") (pin "12") (pinfunction "PA4_12") (pintype "bidirectional"))
    )
    (net (code "66") (name "VBAT") (class "Default")
      (node (ref "C1") (pin "1") (pinfunction "1_1") (pintype "passive"))
      (node (ref "C10") (pin "1") (pinfunction "1_1") (pintype "passive"))
      (node (ref "C18") (pin "2") (pinfunction "2_2") (pintype "passive"))
      (node (ref "C2") (pin "1") (pinfunction "1_1") (pintype "passive"))
      (node (ref "C3") (pin "1") (pinfunction "1_1") (pintype "passive"))
      (node (ref "C4") (pin "1") (pinfunction "1_1") (pintype "passive"))
      (node (ref "C5") (pin "1") (pinfunction "1_1") (pintype "passive"))
      (node (ref "C6") (pin "1") (pinfunction "1_1") (pintype "passive"))
      (node (ref "C7") (pin "1") (pinfunction "1_1") (pintype "passive"))
      (node (ref "C8") (pin "1") (pinfunction "1_1") (pintype "passive"))
      (node (ref "C9") (pin "1") (pinfunction "1_1") (pintype "passive"))
      (node (ref "D1") (pin "2") (pinfunction "K_2") (pintype "passive"))
      (node (ref "P1") (pin "1") (pinfunction "P_1") (pintype "passive"))
      (node (ref "Q1") (pin "5") (pinfunction "D_5") (pintype "passive"))
      (node (ref "Q1") (pin "6") (pinfunction "D_6") (pintype "passive"))
      (node (ref "Q1") (pin "7") (pinfunction "D_7") (pintype "passive"))
      (node (ref "Q1") (pin "8") (pinfunction "D_8") (pintype "passive"))
      (node (ref "Q1") (pin "9") (pinfunction "D_9") (pintype "passive"))
      (node (ref "Q3") (pin "5") (pinfunction "D_5") (pintype "passive"))
      (node (ref "Q3") (pin "6") (pinfunction "D_6") (pintype "passive"))
      (node (ref "Q3") (pin "7") (pinfunction "D_7") (pintype "passive"))
      (node (ref "Q3") (pin "8") (pinfunction "D_8") (pintype "passive"))
      (node (ref "Q3") (pin "9") (pinfunction "D_9") (pintype "passive"))
      (node (ref "Q5") (pin "5") (pinfunction "D_5") (pintype "passive"))
      (node (ref "Q5") (pin "6") (pinfunction "D_6") (pintype "passive"))
      (node (ref "Q5") (pin "7") (pinfunction "D_7") (pintype "passive"))
      (node (ref "Q5") (pin "8") (pinfunction "D_8") (pintype "passive"))
      (node (ref "Q5") (pin "9") (pinfunction "D_9") (pintype "passive"))
      (node (ref "R10") (pin "1") (pinfunction "1_1") (pintype "passive"))
      (node (ref "R13") (pin "2") (pinfunction "2_2") (pintype "passive"))
      (node (ref "U4") (pin "4") (pinfunction "EN_4") (pintype "passive"))
      (node (ref "U4") (pin "5") (pinfunction "VIN_5") (pintype "passive"))
    )
    (net (code "67") (name "unconnected-(U1-NC-Pad4)") (class "Default")
      (node (ref "U1") (pin "4") (pinfunction "NC_4") (pintype "passive+no_connect"))
    )
    (net (code "68") (name "unconnected-(U2-NC-Pad1)") (class "Default")
      (node (ref "U2") (pin "1") (pinfunction "NC_1") (pintype "passive+no_connect"))
    )
    (net (code "69") (name "unconnected-(U3-NC-Pad1)") (class "Default")
      (node (ref "U3") (pin "1") (pinfunction "NC_1") (pintype "passive+no_connect"))
    )
    (net (code "70") (name "unconnected-(U5-MODE-Pad5)") (class "Default")
      (node (ref "U5") (pin "5") (pinfunction "MODE_5") (pintype "passive+no_connect"))
    )
    (net (code "71") (name "unconnected-(U5-NC-Pad7)") (class "Default")
      (node (ref "U5") (pin "7") (pinfunction "NC_7") (pintype "passive+no_connect"))
    )
    (net (code "72") (name "unconnected-(U5-NC-Pad8)") (class "Default")
      (node (ref "U5") (pin "8") (pinfunction "NC_8") (pintype "passive+no_connect"))
    )
    (net (code "73") (name "unconnected-(U7-PA0-Pad8)") (class "Default")
      (node (ref "U7") (pin "8") (pinfunction "PA0_8") (pintype "bidirectional"))
    )
    (net (code "74") (name "unconnected-(U7-PA1-Pad9)") (class "Default")
      (node (ref "U7") (pin "9") (pinfunction "PA1_9") (pintype "bidirectional"))
    )
    (net (code "75") (name "unconnected-(U7-PA3-Pad11)") (class "Default")
      (node (ref "U7") (pin "11") (pinfunction "PA3_11") (pintype "bidirectional"))
    )
    (net (code "76") (name "unconnected-(U7-PA15-Pad38)") (class "Default")
      (node (ref "U7") (pin "38") (pinfunction "PA15_38") (pintype "bidirectional"))
    )
    (net (code "77") (name "unconnected-(U7-PB0-Pad17)") (class "Default")
      (node (ref "U7") (pin "17") (pinfunction "PB0_17") (pintype "bidirectional"))
    )
    (net (code "78") (name "unconnected-(U7-PB1-Pad18)") (class "Default")
      (node (ref "U7") (pin "18") (pinfunction "PB1_18") (pintype "bidirectional"))
    )
    (net (code "79") (name "unconnected-(U7-PB2-Pad19)") (class "Default")
      (node (ref "U7") (pin "19") (pinfunction "PB2_19") (pintype "bidirectional"))
    )
    (net (code "80") (name "unconnected-(U7-PB3-Pad41)") (class "Default")
      (node (ref "U7") (pin "41") (pinfunction "PB3_41") (pintype "bidirectional"))
    )
    (net (code "81") (name "unconnected-(U7-PB4-Pad42)") (class "Default")
      (node (ref "U7") (pin "42") (pinfunction "PB4_42") (pintype "bidirectional"))
    )
    (net (code "82") (name "unconnected-(U7-PB5-Pad43)") (class "Default")
      (node (ref "U7") (pin "43") (pinfunction "PB5_43") (pintype "bidirectional"))
    )
    (net (code "83") (name "unconnected-(U7-PB6-Pad44)") (class "Default")
      (node (ref "U7") (pin "44") (pinfunction "PB6_44") (pintype "bidirectional"))
    )
    (net (code "84") (name "unconnected-(U7-PB7-Pad45)") (class "Default")
      (node (ref "U7") (pin "45") (pinfunction "PB7_45") (pintype "bidirectional"))
    )
    (net (code "85") (name "unconnected-(U7-PB10-Pad22)") (class "Default")
      (node (ref "U7") (pin "22") (pinfunction "PB10_22") (pintype "bidirectional"))
    )
    (net (code "86") (name "unconnected-(U7-PB12-Pad25)") (class "Default")
      (node (ref "U7") (pin "25") (pinfunction "PB12_25") (pintype "bidirectional"))
    )
    (net (code "87") (name "unconnected-(U7-PC6-Pad29)") (class "Default")
      (node (ref "U7") (pin "29") (pinfunction "PC6_29") (pintype "bidirectional"))
    )
    (net (code "88") (name "unconnected-(U7-PC10-Pad39)") (class "Default")
      (node (ref "U7") (pin "39") (pinfunction "PC10_39") (pintype "bidirectional"))
    )
    (net (code "89") (name "unconnected-(U7-PC11-Pad40)") (class "Default")
      (node (ref "U7") (pin "40") (pinfunction "PC11_40") (pintype "bidirectional"))
    )
    (net (code "90") (name "unconnected-(U7-PC13-Pad2)") (class "Default")
      (node (ref "U7") (pin "2") (pinfunction "PC13_2") (pintype "bidirectional"))
    )
    (net (code "91") (name "unconnected-(U7-PC14-OSC32_IN-Pad3)") (class "Default")
      (node (ref "U7") (pin "3") (pinfunction "PC14-OSC32_IN_3") (pintype "bidirectional"))
    )
    (net (code "92") (name "unconnected-(U7-PC15-OSC32_OUT-Pad4)") (class "Default")
      (node (ref "U7") (pin "4") (pinfunction "PC15-OSC32_OUT_4") (pintype "bidirectional"))
    )
    (net (code "93") (name "unconnected-(U8-A-Pad16)") (class "Default")
      (node (ref "U8") (pin "16") (pinfunction "A_16") (pintype "passive+no_connect"))
    )
    (net (code "94") (name "unconnected-(U8-B-Pad15)") (class "Default")
      (node (ref "U8") (pin "15") (pinfunction "B_15") (pintype "passive+no_connect"))
    )
    (net (code "95") (name "unconnected-(U8-ERROR-Pad13)") (class "Default")
      (node (ref "U8") (pin "13") (pinfunction "ERROR_13") (pintype "passive+no_connect"))
    )
    (net (code "96") (name "unconnected-(U8-HVPP-Pad4)") (class "Default")
      (node (ref "U8") (pin "4") (pinfunction "HVPP_4") (pintype "passive+no_connect"))
    )
    (net (code "97") (name "unconnected-(U8-OUT-Pad10)") (class "Default")
      (node (ref "U8") (pin "10") (pinfunction "OUT_10") (pintype "passive+no_connect"))
    )
    (net (code "98") (name "unconnected-(U8-TEST-Pad11)") (class "Default")
      (node (ref "U8") (pin "11") (pinfunction "TEST_11") (pintype "passive+no_connect"))
    )
    (net (code "99") (name "unconnected-(U8-U-Pad1)") (class "Default")
      (node (ref "U8") (pin "1") (pinfunction "U_1") (pintype "passive+no_connect"))
    )
    (net (code "100") (name "unconnected-(U8-V-Pad2)") (class "Default")
      (node (ref "U8") (pin "2") (pinfunction "V_2") (pintype "passive+no_connect"))
    )
    (net (code "101") (name "unconnected-(U8-W-Pad3)") (class "Default")
      (node (ref "U8") (pin "3") (pinfunction "W_3") (pintype "passive+no_connect"))
    )
    (net (code "102") (name "unconnected-(U8-Z-Pad14)") (class "Default")
      (node (ref "U8") (pin "14") (pinfunction "Z_14") (pintype "passive+no_connect"))
    )
    (net (code "103") (name "unconnected-(USB1-SBU1-PadA8)") (class "Default")
      (node (ref "USB1") (pin "A8") (pinfunction "SBU1_A8") (pintype "passive+no_connect"))
    )
    (net (code "104") (name "unconnected-(USB1-SBU2-PadB8)") (class "Default")
      (node (ref "USB1") (pin "B8") (pinfunction "SBU2_B8") (pintype "passive+no_connect"))
    )
  )
)
